# RasPi-powerSys.net
KiCad netlist of a schematic drawn in EAGLE
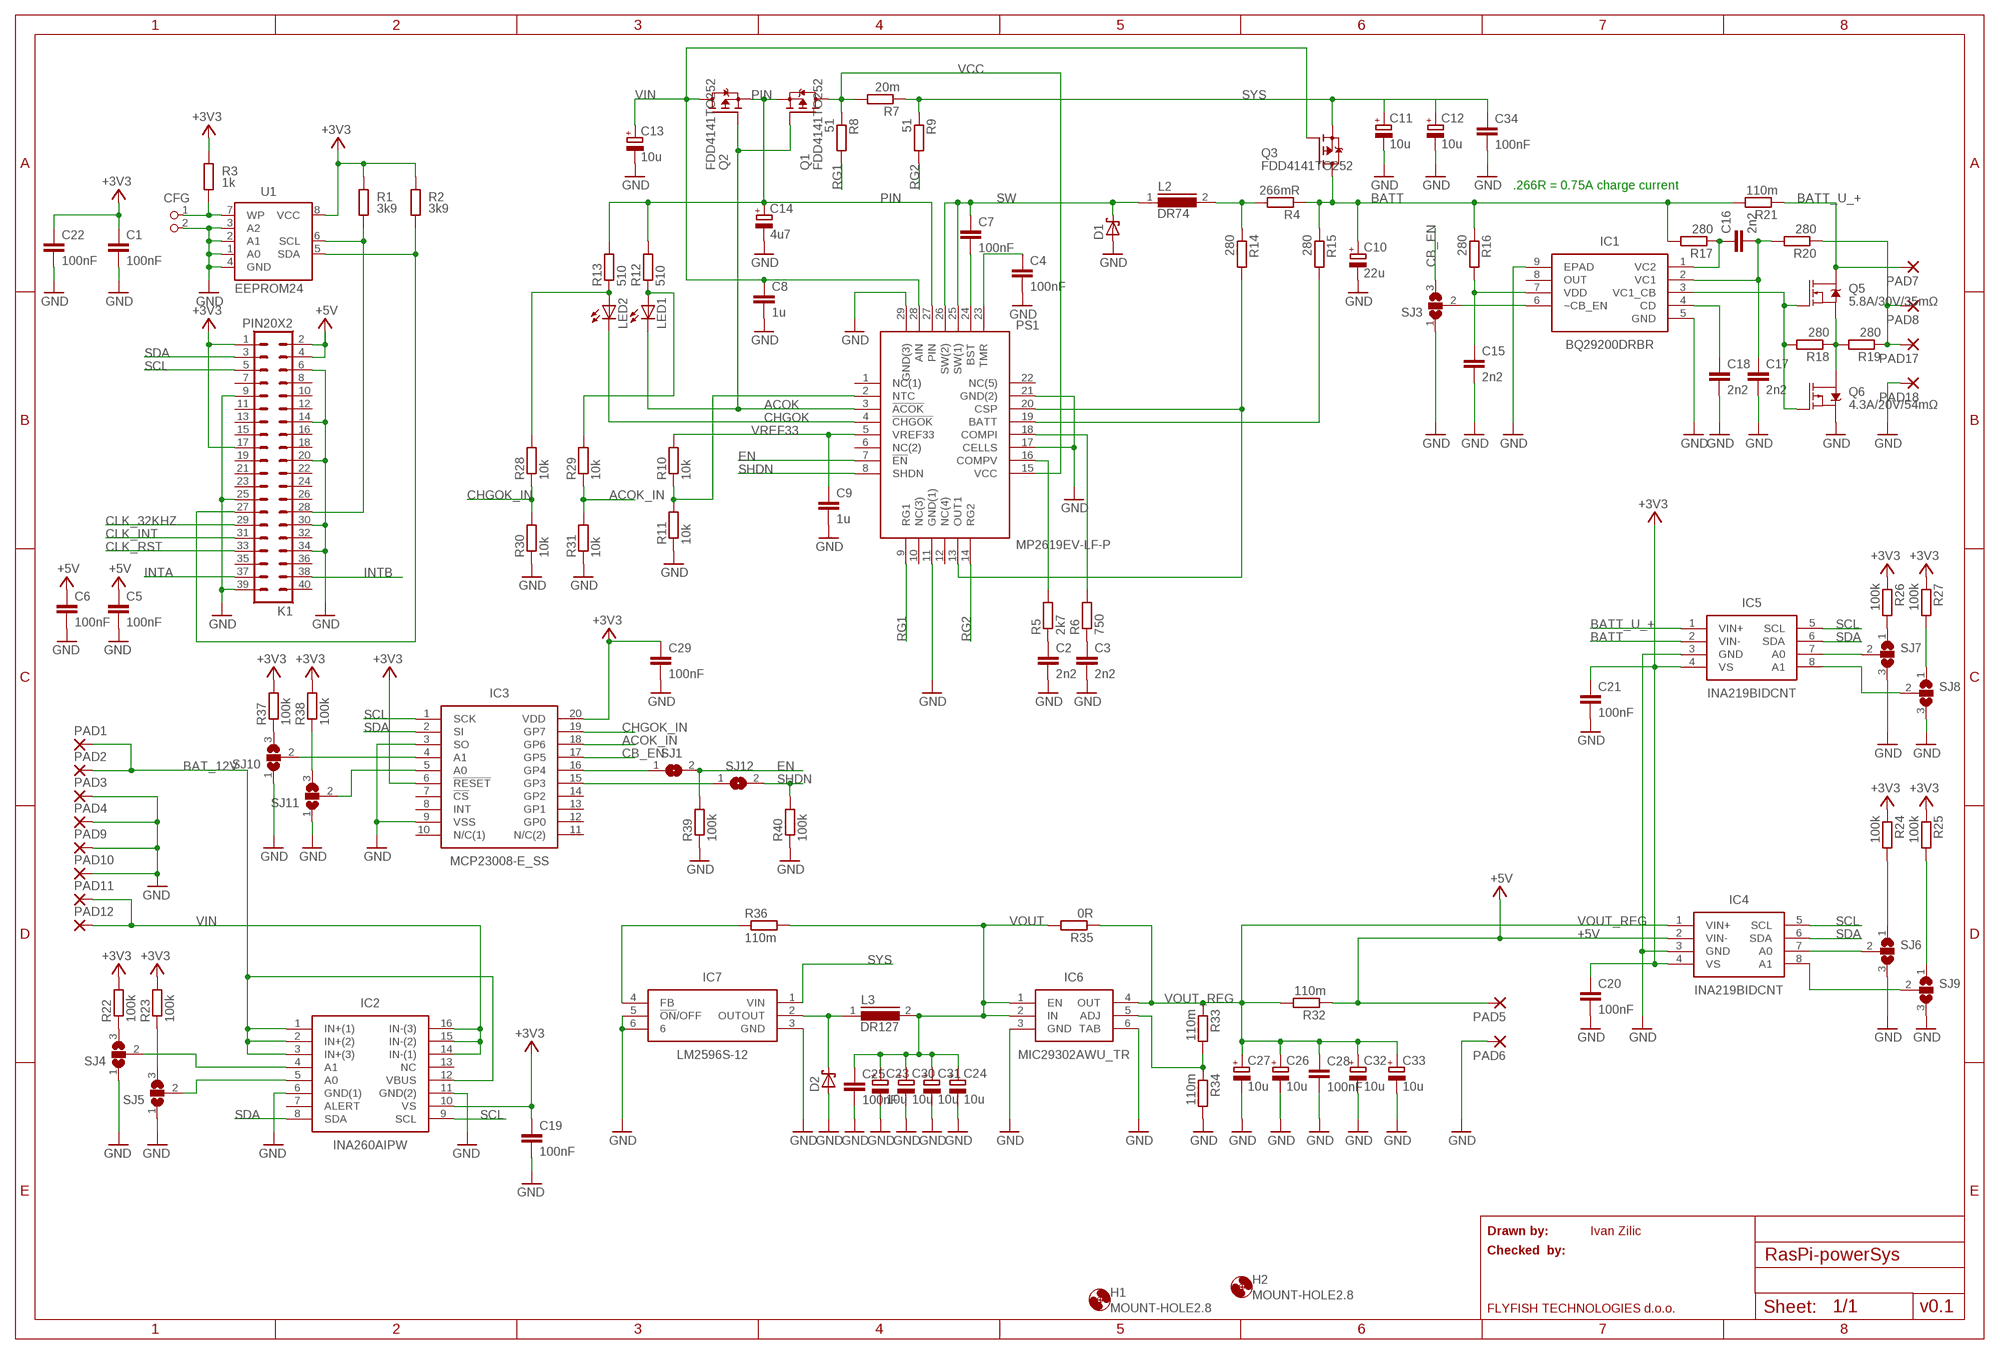
[diagram p0: schematic, sheet 1]

(export (version "E")
  (design (tool "Eeschema 10.0.6"))
  (components
    (comp (ref "C1")
      (value "100nF")
      (footprint "eagle-import:C0805K")
      (libsource (lib "eagle-import") (part "C-EUC0805K"))
    )
    (comp (ref "C2")
      (value "2n2")
      (footprint "eagle-import:C0805K")
      (libsource (lib "eagle-import") (part "C-EUC0805K"))
    )
    (comp (ref "C3")
      (value "2n2")
      (footprint "eagle-import:C0805K")
      (libsource (lib "eagle-import") (part "C-EUC0805K"))
    )
    (comp (ref "C4")
      (value "100nF")
      (footprint "eagle-import:C0805K")
      (libsource (lib "eagle-import") (part "C-EUC0805K"))
    )
    (comp (ref "C5")
      (value "100nF")
      (footprint "eagle-import:C0805K")
      (libsource (lib "eagle-import") (part "C-EUC0805K"))
    )
    (comp (ref "C6")
      (value "100nF")
      (footprint "eagle-import:C0805K")
      (libsource (lib "eagle-import") (part "C-EUC0805K"))
    )
    (comp (ref "C7")
      (value "100nF")
      (footprint "eagle-import:C0805K")
      (libsource (lib "eagle-import") (part "C-EUC0805K"))
    )
    (comp (ref "C8")
      (value "1u")
      (footprint "eagle-import:C0805K")
      (libsource (lib "eagle-import") (part "C-EUC0805K"))
    )
    (comp (ref "C9")
      (value "1u")
      (footprint "eagle-import:C0805K")
      (libsource (lib "eagle-import") (part "C-EUC0805K"))
    )
    (comp (ref "C10")
      (value "22u")
      (footprint "eagle-import:SMC_D")
      (libsource (lib "eagle-import") (part "CPOL-EUSMCD"))
    )
    (comp (ref "C11")
      (value "10u")
      (footprint "eagle-import:SMC_E")
      (libsource (lib "eagle-import") (part "CPOL-EUSMCE"))
    )
    (comp (ref "C12")
      (value "10u")
      (footprint "eagle-import:SMC_D")
      (libsource (lib "eagle-import") (part "CPOL-EUSMCD"))
    )
    (comp (ref "C13")
      (value "10u")
      (footprint "eagle-import:SMC_D")
      (libsource (lib "eagle-import") (part "CPOL-EUSMCD"))
    )
    (comp (ref "C14")
      (value "4u7")
      (footprint "eagle-import:SMC_D")
      (libsource (lib "eagle-import") (part "CPOL-EUSMCD"))
    )
    (comp (ref "C15")
      (value "2n2")
      (footprint "eagle-import:C0805K")
      (libsource (lib "eagle-import") (part "C-EUC0805K"))
    )
    (comp (ref "C16")
      (value "2n2")
      (footprint "eagle-import:C0805K")
      (libsource (lib "eagle-import") (part "C-EUC0805K"))
    )
    (comp (ref "C17")
      (value "2n2")
      (footprint "eagle-import:C0805K")
      (libsource (lib "eagle-import") (part "C-EUC0805K"))
    )
    (comp (ref "C18")
      (value "2n2")
      (footprint "eagle-import:C0805K")
      (libsource (lib "eagle-import") (part "C-EUC0805K"))
    )
    (comp (ref "C19")
      (value "100nF")
      (footprint "eagle-import:C0805K")
      (libsource (lib "eagle-import") (part "C-EUC0805K"))
    )
    (comp (ref "C20")
      (value "100nF")
      (footprint "eagle-import:C0805K")
      (libsource (lib "eagle-import") (part "C-EUC0805K"))
    )
    (comp (ref "C21")
      (value "100nF")
      (footprint "eagle-import:C0805K")
      (libsource (lib "eagle-import") (part "C-EUC0805K"))
    )
    (comp (ref "C22")
      (value "100nF")
      (footprint "eagle-import:C0805K")
      (libsource (lib "eagle-import") (part "C-EUC0805K"))
    )
    (comp (ref "C23")
      (value "10u")
      (footprint "eagle-import:SMC_E")
      (libsource (lib "eagle-import") (part "CPOL-EUSMCE"))
    )
    (comp (ref "C24")
      (value "10u")
      (footprint "eagle-import:SMC_E")
      (libsource (lib "eagle-import") (part "CPOL-EUSMCE"))
    )
    (comp (ref "C25")
      (value "100nF")
      (footprint "eagle-import:C0805K")
      (libsource (lib "eagle-import") (part "C-EUC0805K"))
    )
    (comp (ref "C26")
      (value "10u")
      (footprint "eagle-import:SMC_E")
      (libsource (lib "eagle-import") (part "CPOL-EUSMCE"))
    )
    (comp (ref "C27")
      (value "10u")
      (footprint "eagle-import:SMC_E")
      (libsource (lib "eagle-import") (part "CPOL-EUSMCE"))
    )
    (comp (ref "C28")
      (value "100nF")
      (footprint "eagle-import:C0805K")
      (libsource (lib "eagle-import") (part "C-EUC0805K"))
    )
    (comp (ref "C29")
      (value "100nF")
      (footprint "eagle-import:C0805K")
      (libsource (lib "eagle-import") (part "C-EUC0805K"))
    )
    (comp (ref "C30")
      (value "10u")
      (footprint "eagle-import:SMC_E")
      (libsource (lib "eagle-import") (part "CPOL-EUSMCE"))
    )
    (comp (ref "C31")
      (value "10u")
      (footprint "eagle-import:SMC_E")
      (libsource (lib "eagle-import") (part "CPOL-EUSMCE"))
    )
    (comp (ref "C32")
      (value "10u")
      (footprint "eagle-import:SMC_E")
      (libsource (lib "eagle-import") (part "CPOL-EUSMCE"))
    )
    (comp (ref "C33")
      (value "10u")
      (footprint "eagle-import:SMC_E")
      (libsource (lib "eagle-import") (part "CPOL-EUSMCE"))
    )
    (comp (ref "C34")
      (value "100nF")
      (footprint "eagle-import:C0805K")
      (libsource (lib "eagle-import") (part "C-EUC0805K"))
    )
    (comp (ref "CFG")
      (value "PIN2_100")
      (footprint "eagle-import:PIN_W_2")
      (libsource (lib "eagle-import") (part "PIN2_100"))
    )
    (comp (ref "D1")
      (value "SCHOTTKY-DIODESMD")
      (footprint "eagle-import:SMB")
      (libsource (lib "eagle-import") (part "SCHOTTKY-DIODESMD"))
    )
    (comp (ref "D2")
      (value "SCHOTTKY-DIODESMD")
      (footprint "eagle-import:SMB")
      (libsource (lib "eagle-import") (part "SCHOTTKY-DIODESMD"))
    )
    (comp (ref "H1")
      (value "MOUNT-HOLE2.8")
      (footprint "eagle-import:2,8")
      (libsource (lib "eagle-import") (part "MOUNT-HOLE2.8"))
    )
    (comp (ref "H2")
      (value "MOUNT-HOLE2.8")
      (footprint "eagle-import:2,8")
      (libsource (lib "eagle-import") (part "MOUNT-HOLE2.8"))
    )
    (comp (ref "IC1")
      (value "BQ29200DRBR")
      (footprint "eagle-import:SON65P300X300X100-9N")
      (libsource (lib "eagle-import") (part "BQ29200DRBR"))
    )
    (comp (ref "IC2")
      (value "INA260AIPW")
      (footprint "eagle-import:SOP65P640X120-16N")
      (libsource (lib "eagle-import") (part "INA260AIPW"))
    )
    (comp (ref "IC3")
      (value "MCP23008-E_SS")
      (footprint "eagle-import:SOP65P780X200-20N")
      (fields
        (field (name "MANUFACTURER_PART_NUMBER") "MCP23008-E/SS")
        (field (name "RS_PART_NUMBER") "7709707")
      )
      (libsource (lib "eagle-import") (part "MCP23008-E_SS"))
    )
    (comp (ref "IC4")
      (value "INA219BIDCNT")
      (footprint "eagle-import:SOT65P280X145-8N")
      (fields (field (name "RS_PART_NUMBER") "7300556P"))
      (libsource (lib "eagle-import") (part "INA219BIDCNT"))
    )
    (comp (ref "IC5")
      (value "INA219BIDCNT")
      (footprint "eagle-import:SOT65P280X145-8N")
      (fields (field (name "RS_PART_NUMBER") "7300556P"))
      (libsource (lib "eagle-import") (part "INA219BIDCNT"))
    )
    (comp (ref "IC6")
      (value "MIC29302AWU_TR")
      (footprint "eagle-import:5-PIN-TO-263(U)")
      (fields
        (field (name "MANUFACTURER_PART_NUMBER") "MIC29302AWU TR")
        (field (name "RS_PART_NUMBER") "8855990")
      )
      (libsource (lib "eagle-import") (part "MIC29302AWU_TR"))
    )
    (comp (ref "IC7")
      (value "LM2596S-12")
      (footprint "eagle-import:5-PIN-TO-263(U)")
      (libsource (lib "eagle-import") (part "LM2596S-12"))
    )
    (comp (ref "K1")
      (value "PIN20X2")
      (footprint "eagle-import:PIN_20X2")
      (libsource (lib "eagle-import") (part "PIN20X2"))
    )
    (comp (ref "L2")
      (value "DR74")
      (footprint "eagle-import:DR74")
      (libsource (lib "eagle-import") (part "DR74"))
    )
    (comp (ref "L3")
      (value "DR127")
      (footprint "eagle-import:DR127")
      (libsource (lib "eagle-import") (part "DR127"))
    )
    (comp (ref "LED1")
      (value "LEDCHIPLED_0805")
      (footprint "eagle-import:CHIPLED_0805")
      (libsource (lib "eagle-import") (part "LEDCHIPLED_0805"))
    )
    (comp (ref "LED2")
      (value "LEDCHIPLED_0805")
      (footprint "eagle-import:CHIPLED_0805")
      (libsource (lib "eagle-import") (part "LEDCHIPLED_0805"))
    )
    (comp (ref "PAD1")
      (value "3,81/1,4")
      (footprint "eagle-import:3,81_1,4")
      (libsource (lib "eagle-import") (part "3,81/1,4"))
    )
    (comp (ref "PAD2")
      (value "3,81/1,4")
      (footprint "eagle-import:3,81_1,4")
      (libsource (lib "eagle-import") (part "3,81/1,4"))
    )
    (comp (ref "PAD3")
      (value "3,81/1,4")
      (footprint "eagle-import:3,81_1,4")
      (libsource (lib "eagle-import") (part "3,81/1,4"))
    )
    (comp (ref "PAD4")
      (value "3,81/1,4")
      (footprint "eagle-import:3,81_1,4")
      (libsource (lib "eagle-import") (part "3,81/1,4"))
    )
    (comp (ref "PAD5")
      (value "3,81/1,4")
      (footprint "eagle-import:3,81_1,4")
      (libsource (lib "eagle-import") (part "3,81/1,4"))
    )
    (comp (ref "PAD6")
      (value "3,81/1,4")
      (footprint "eagle-import:3,81_1,4")
      (libsource (lib "eagle-import") (part "3,81/1,4"))
    )
    (comp (ref "PAD7")
      (value "3,81/1,4")
      (footprint "eagle-import:3,81_1,4")
      (libsource (lib "eagle-import") (part "3,81/1,4"))
    )
    (comp (ref "PAD8")
      (value "3,81/1,4")
      (footprint "eagle-import:3,81_1,4")
      (libsource (lib "eagle-import") (part "3,81/1,4"))
    )
    (comp (ref "PAD9")
      (value "3,81/1,4")
      (footprint "eagle-import:3,81_1,4")
      (libsource (lib "eagle-import") (part "3,81/1,4"))
    )
    (comp (ref "PAD10")
      (value "3,81/1,4")
      (footprint "eagle-import:3,81_1,4")
      (libsource (lib "eagle-import") (part "3,81/1,4"))
    )
    (comp (ref "PAD11")
      (value "3,81/1,4")
      (footprint "eagle-import:3,81_1,4")
      (libsource (lib "eagle-import") (part "3,81/1,4"))
    )
    (comp (ref "PAD12")
      (value "3,81/1,4")
      (footprint "eagle-import:3,81_1,4")
      (libsource (lib "eagle-import") (part "3,81/1,4"))
    )
    (comp (ref "PAD17")
      (value "3,81/1,4")
      (footprint "eagle-import:3,81_1,4")
      (libsource (lib "eagle-import") (part "3,81/1,4"))
    )
    (comp (ref "PAD18")
      (value "3,81/1,4")
      (footprint "eagle-import:3,81_1,4")
      (libsource (lib "eagle-import") (part "3,81/1,4"))
    )
    (comp (ref "PS1")
      (value "MP2619EV-LF-P")
      (footprint "eagle-import:QFN50P400X500X100-29N")
      (libsource (lib "eagle-import") (part "MP2619EV-LF-P"))
    )
    (comp (ref "Q1")
      (value "FDD4141TO252")
      (footprint "eagle-import:TO252")
      (libsource (lib "eagle-import") (part "FDD4141TO252"))
    )
    (comp (ref "Q2")
      (value "FDD4141TO252")
      (footprint "eagle-import:TO252")
      (libsource (lib "eagle-import") (part "FDD4141TO252"))
    )
    (comp (ref "Q3")
      (value "FDD4141TO252")
      (footprint "eagle-import:TO252")
      (libsource (lib "eagle-import") (part "FDD4141TO252"))
    )
    (comp (ref "Q5")
      (value "5.8A/30V/35mΩ")
      (footprint "eagle-import:SOT23-3")
      (libsource (lib "eagle-import") (part "MOSFET-NCH-AO3404A"))
    )
    (comp (ref "Q6")
      (value "4.3A/20V/54mΩ")
      (footprint "eagle-import:SOT23-3")
      (libsource (lib "eagle-import") (part "MOSFET_PCH-IRLML2244"))
    )
    (comp (ref "R1")
      (value "3k9")
      (footprint "eagle-import:M0805")
      (fields (field (name "TOLERANCE") "5%"))
      (libsource (lib "eagle-import") (part "resistor_348_R-EU_M0805"))
    )
    (comp (ref "R2")
      (value "3k9")
      (footprint "eagle-import:M0805")
      (fields (field (name "TOLERANCE") "5%"))
      (libsource (lib "eagle-import") (part "resistor_348_R-EU_M0805"))
    )
    (comp (ref "R3")
      (value "1k")
      (footprint "eagle-import:M0805")
      (fields (field (name "TOLERANCE") "5%"))
      (libsource (lib "eagle-import") (part "resistor_348_R-EU_M0805"))
    )
    (comp (ref "R4")
      (value "266mR")
      (footprint "eagle-import:R1206")
      (libsource (lib "eagle-import") (part "R-EU_R1206"))
    )
    (comp (ref "R5")
      (value "2k7")
      (footprint "eagle-import:R0805")
      (libsource (lib "eagle-import") (part "R-EU_R0805"))
    )
    (comp (ref "R6")
      (value "750")
      (footprint "eagle-import:R0805")
      (libsource (lib "eagle-import") (part "R-EU_R0805"))
    )
    (comp (ref "R7")
      (value "20m")
      (footprint "eagle-import:R0805")
      (libsource (lib "eagle-import") (part "R-EU_R0805"))
    )
    (comp (ref "R8")
      (value "51")
      (footprint "eagle-import:R0805")
      (libsource (lib "eagle-import") (part "R-EU_R0805"))
    )
    (comp (ref "R9")
      (value "51")
      (footprint "eagle-import:R0805")
      (libsource (lib "eagle-import") (part "R-EU_R0805"))
    )
    (comp (ref "R10")
      (value "10k")
      (footprint "eagle-import:R0805")
      (libsource (lib "eagle-import") (part "R-EU_R0805"))
    )
    (comp (ref "R11")
      (value "10k")
      (footprint "eagle-import:R0805")
      (libsource (lib "eagle-import") (part "R-EU_R0805"))
    )
    (comp (ref "R12")
      (value "510")
      (footprint "eagle-import:R0805")
      (libsource (lib "eagle-import") (part "R-EU_R0805"))
    )
    (comp (ref "R13")
      (value "510")
      (footprint "eagle-import:R0805")
      (libsource (lib "eagle-import") (part "R-EU_R0805"))
    )
    (comp (ref "R14")
      (value "280")
      (footprint "eagle-import:R0805")
      (libsource (lib "eagle-import") (part "R-EU_R0805"))
    )
    (comp (ref "R15")
      (value "280")
      (footprint "eagle-import:R0805")
      (libsource (lib "eagle-import") (part "R-EU_R0805"))
    )
    (comp (ref "R16")
      (value "280")
      (footprint "eagle-import:R0805")
      (libsource (lib "eagle-import") (part "R-EU_R0805"))
    )
    (comp (ref "R17")
      (value "280")
      (footprint "eagle-import:R1206")
      (libsource (lib "eagle-import") (part "R-EU_R1206"))
    )
    (comp (ref "R18")
      (value "280")
      (footprint "eagle-import:R1206")
      (libsource (lib "eagle-import") (part "R-EU_R1206"))
    )
    (comp (ref "R19")
      (value "280")
      (footprint "eagle-import:R1206")
      (libsource (lib "eagle-import") (part "R-EU_R1206"))
    )
    (comp (ref "R20")
      (value "280")
      (footprint "eagle-import:R1206")
      (libsource (lib "eagle-import") (part "R-EU_R1206"))
    )
    (comp (ref "R21")
      (value "110m")
      (footprint "eagle-import:R0805")
      (libsource (lib "eagle-import") (part "R-EU_R0805"))
    )
    (comp (ref "R22")
      (value "100k")
      (footprint "eagle-import:R0805")
      (libsource (lib "eagle-import") (part "R-EU_R0805"))
    )
    (comp (ref "R23")
      (value "100k")
      (footprint "eagle-import:R0805")
      (libsource (lib "eagle-import") (part "R-EU_R0805"))
    )
    (comp (ref "R24")
      (value "100k")
      (footprint "eagle-import:R0805")
      (libsource (lib "eagle-import") (part "R-EU_R0805"))
    )
    (comp (ref "R25")
      (value "100k")
      (footprint "eagle-import:R0805")
      (libsource (lib "eagle-import") (part "R-EU_R0805"))
    )
    (comp (ref "R26")
      (value "100k")
      (footprint "eagle-import:R0805")
      (libsource (lib "eagle-import") (part "R-EU_R0805"))
    )
    (comp (ref "R27")
      (value "100k")
      (footprint "eagle-import:R0805")
      (libsource (lib "eagle-import") (part "R-EU_R0805"))
    )
    (comp (ref "R28")
      (value "10k")
      (footprint "eagle-import:R0805")
      (libsource (lib "eagle-import") (part "R-EU_R0805"))
    )
    (comp (ref "R29")
      (value "10k")
      (footprint "eagle-import:R0805")
      (libsource (lib "eagle-import") (part "R-EU_R0805"))
    )
    (comp (ref "R30")
      (value "10k")
      (footprint "eagle-import:R0805")
      (libsource (lib "eagle-import") (part "R-EU_R0805"))
    )
    (comp (ref "R31")
      (value "10k")
      (footprint "eagle-import:R0805")
      (libsource (lib "eagle-import") (part "R-EU_R0805"))
    )
    (comp (ref "R32")
      (value "110m")
      (footprint "eagle-import:R1206")
      (libsource (lib "eagle-import") (part "R-EU_R1206"))
    )
    (comp (ref "R33")
      (value "110m")
      (footprint "eagle-import:R0805")
      (libsource (lib "eagle-import") (part "R-EU_R0805"))
    )
    (comp (ref "R34")
      (value "110m")
      (footprint "eagle-import:R0805")
      (libsource (lib "eagle-import") (part "R-EU_R0805"))
    )
    (comp (ref "R35")
      (value "0R")
      (footprint "eagle-import:R1206")
      (libsource (lib "eagle-import") (part "R-EU_R1206"))
    )
    (comp (ref "R36")
      (value "110m")
      (footprint "eagle-import:R0805")
      (libsource (lib "eagle-import") (part "R-EU_R0805"))
    )
    (comp (ref "R37")
      (value "100k")
      (footprint "eagle-import:R0805")
      (libsource (lib "eagle-import") (part "R-EU_R0805"))
    )
    (comp (ref "R38")
      (value "100k")
      (footprint "eagle-import:R0805")
      (libsource (lib "eagle-import") (part "R-EU_R0805"))
    )
    (comp (ref "R39")
      (value "100k")
      (footprint "eagle-import:R0805")
      (libsource (lib "eagle-import") (part "R-EU_R0805"))
    )
    (comp (ref "R40")
      (value "100k")
      (footprint "eagle-import:R0805")
      (libsource (lib "eagle-import") (part "R-EU_R0805"))
    )
    (comp (ref "SJ1") (value "SJ") (footprint "eagle-import:SJ") (libsource (lib "eagle-import") (part "SJ")))
    (comp (ref "SJ3")
      (value "SJ2W")
      (footprint "eagle-import:SJ_2")
      (libsource (lib "eagle-import") (part "SJ2W"))
    )
    (comp (ref "SJ4")
      (value "SJ2W")
      (footprint "eagle-import:SJ_2")
      (libsource (lib "eagle-import") (part "SJ2W"))
    )
    (comp (ref "SJ5")
      (value "SJ2W")
      (footprint "eagle-import:SJ_2")
      (libsource (lib "eagle-import") (part "SJ2W"))
    )
    (comp (ref "SJ6")
      (value "SJ2W")
      (footprint "eagle-import:SJ_2")
      (libsource (lib "eagle-import") (part "SJ2W"))
    )
    (comp (ref "SJ7")
      (value "SJ2W")
      (footprint "eagle-import:SJ_2")
      (libsource (lib "eagle-import") (part "SJ2W"))
    )
    (comp (ref "SJ8")
      (value "SJ2W")
      (footprint "eagle-import:SJ_2")
      (libsource (lib "eagle-import") (part "SJ2W"))
    )
    (comp (ref "SJ9")
      (value "SJ2W")
      (footprint "eagle-import:SJ_2")
      (libsource (lib "eagle-import") (part "SJ2W"))
    )
    (comp (ref "SJ10")
      (value "SJ2W")
      (footprint "eagle-import:SJ_2")
      (libsource (lib "eagle-import") (part "SJ2W"))
    )
    (comp (ref "SJ11")
      (value "SJ2W")
      (footprint "eagle-import:SJ_2")
      (libsource (lib "eagle-import") (part "SJ2W"))
    )
    (comp (ref "SJ12")
      (value "SJ")
      (footprint "eagle-import:SJ")
      (libsource (lib "eagle-import") (part "SJ"))
    )
    (comp (ref "U1")
      (value "EEPROM24")
      (footprint "eagle-import:SOIC8")
      (libsource (lib "eagle-import") (part "EEPROM24"))
    )
  )
  (nets
    (net (code "1") (name "+3V3") (class "Default")
      (node (ref "C1") (pin "1") (pinfunction "1_1") (pintype "passive"))
      (node (ref "C19") (pin "1") (pinfunction "1_1") (pintype "passive"))
      (node (ref "C20") (pin "1") (pinfunction "1_1") (pintype "passive"))
      (node (ref "C21") (pin "1") (pinfunction "1_1") (pintype "passive"))
      (node (ref "C22") (pin "1") (pinfunction "1_1") (pintype "passive"))
      (node (ref "C29") (pin "1") (pinfunction "1_1") (pintype "passive"))
      (node (ref "IC2") (pin "10") (pinfunction "VS_10") (pintype "power_in"))
      (node (ref "IC3") (pin "20") (pinfunction "VDD_20") (pintype "passive"))
      (node (ref "IC3") (pin "6") (pinfunction "~{RESET}_6") (pintype "passive"))
      (node (ref "IC4") (pin "4") (pinfunction "VS_4") (pintype "passive"))
      (node (ref "IC5") (pin "4") (pinfunction "VS_4") (pintype "passive"))
      (node (ref "K1") (pin "1") (pinfunction "1_1") (pintype "passive"))
      (node (ref "K1") (pin "17") (pinfunction "17_17") (pintype "passive"))
      (node (ref "R1") (pin "2") (pinfunction "2_2") (pintype "passive"))
      (node (ref "R2") (pin "2") (pinfunction "2_2") (pintype "passive"))
      (node (ref "R22") (pin "2") (pinfunction "2_2") (pintype "passive"))
      (node (ref "R23") (pin "2") (pinfunction "2_2") (pintype "passive"))
      (node (ref "R24") (pin "1") (pinfunction "1_1") (pintype "passive"))
      (node (ref "R25") (pin "1") (pinfunction "1_1") (pintype "passive"))
      (node (ref "R26") (pin "1") (pinfunction "1_1") (pintype "passive"))
      (node (ref "R27") (pin "1") (pinfunction "1_1") (pintype "passive"))
      (node (ref "R3") (pin "2") (pinfunction "2_2") (pintype "passive"))
      (node (ref "R37") (pin "2") (pinfunction "2_2") (pintype "passive"))
      (node (ref "R38") (pin "2") (pinfunction "2_2") (pintype "passive"))
      (node (ref "U1") (pin "8") (pinfunction "VCC_8") (pintype "power_in"))
    )
    (net (code "2") (name "+5V") (class "Default")
      (node (ref "C5") (pin "1") (pinfunction "1_1") (pintype "passive"))
      (node (ref "C6") (pin "1") (pinfunction "1_1") (pintype "passive"))
      (node (ref "IC4") (pin "2") (pinfunction "VIN-_2") (pintype "input"))
      (node (ref "K1") (pin "2") (pinfunction "2_2") (pintype "passive"))
      (node (ref "K1") (pin "4") (pinfunction "4_4") (pintype "passive"))
      (node (ref "PAD5") (pin "1") (pinfunction "P_1") (pintype "passive"))
      (node (ref "R32") (pin "1") (pinfunction "1_1") (pintype "passive"))
    )
    (net (code "3") (name "/ACOK") (class "Default")
      (node (ref "LED1") (pin "C") (pinfunction "C_C") (pintype "passive"))
      (node (ref "PS1") (pin "3") (pinfunction "~{ACOK}_3") (pintype "output"))
      (node (ref "Q1") (pin "1") (pinfunction "G_1") (pintype "passive"))
      (node (ref "Q2") (pin "1") (pinfunction "G_1") (pintype "passive"))
    )
    (net (code "4") (name "/ACOK_IN") (class "Default")
      (node (ref "IC3") (pin "18") (pinfunction "GP6_18") (pintype "passive"))
      (node (ref "R29") (pin "1") (pinfunction "1_1") (pintype "passive"))
      (node (ref "R31") (pin "2") (pinfunction "2_2") (pintype "passive"))
    )
    (net (code "5") (name "/BATT") (class "Default")
      (node (ref "C10") (pin "+") (pinfunction "+_+") (pintype "passive"))
      (node (ref "IC5") (pin "2") (pinfunction "VIN-_2") (pintype "input"))
      (node (ref "Q3") (pin "3") (pinfunction "D_3") (pintype "passive"))
      (node (ref "R15") (pin "1") (pinfunction "1_1") (pintype "passive"))
      (node (ref "R16") (pin "1") (pinfunction "1_1") (pintype "passive"))
      (node (ref "R17") (pin "2") (pinfunction "2_2") (pintype "passive"))
      (node (ref "R21") (pin "2") (pinfunction "2_2") (pintype "passive"))
      (node (ref "R4") (pin "1") (pinfunction "1_1") (pintype "passive"))
    )
    (net (code "6") (name "/BATT_U_+") (class "Default")
      (node (ref "IC5") (pin "1") (pinfunction "VIN+_1") (pintype "input"))
      (node (ref "PAD7") (pin "1") (pinfunction "P_1") (pintype "passive"))
      (node (ref "Q5") (pin "3") (pinfunction "D_3") (pintype "bidirectional"))
      (node (ref "R21") (pin "1") (pinfunction "1_1") (pintype "passive"))
    )
    (net (code "7") (name "/BAT_12V") (class "Default")
      (node (ref "IC2") (pin "1") (pinfunction "IN+(1)_1") (pintype "bidirectional"))
      (node (ref "IC2") (pin "12") (pinfunction "VBUS_12") (pintype "power_in"))
      (node (ref "IC2") (pin "2") (pinfunction "IN+(2)_2") (pintype "bidirectional"))
      (node (ref "IC2") (pin "3") (pinfunction "IN+(3)_3") (pintype "bidirectional"))
      (node (ref "PAD1") (pin "1") (pinfunction "P_1") (pintype "passive"))
      (node (ref "PAD2") (pin "1") (pinfunction "P_1") (pintype "passive"))
    )
    (net (code "8") (name "/CB_EN") (class "Default")
      (node (ref "IC3") (pin "17") (pinfunction "GP5_17") (pintype "passive"))
      (node (ref "SJ3") (pin "3") (pinfunction "3_3") (pintype "passive"))
    )
    (net (code "9") (name "/CHGOK") (class "Default")
      (node (ref "LED2") (pin "C") (pinfunction "C_C") (pintype "passive"))
      (node (ref "PS1") (pin "4") (pinfunction "~{CHGOK}_4") (pintype "output"))
    )
    (net (code "10") (name "/CHGOK_IN") (class "Default")
      (node (ref "IC3") (pin "19") (pinfunction "GP7_19") (pintype "passive"))
      (node (ref "R28") (pin "1") (pinfunction "1_1") (pintype "passive"))
      (node (ref "R30") (pin "2") (pinfunction "2_2") (pintype "passive"))
    )
    (net (code "11") (name "/CLK_32KHZ") (class "Default")
      (node (ref "K1") (pin "29") (pinfunction "29_29") (pintype "passive"))
    )
    (net (code "12") (name "/CLK_INT") (class "Default")
      (node (ref "K1") (pin "31") (pinfunction "31_31") (pintype "passive"))
    )
    (net (code "13") (name "/CLK_RST") (class "Default")
      (node (ref "K1") (pin "33") (pinfunction "33_33") (pintype "passive"))
    )
    (net (code "14") (name "/EN") (class "Default")
      (node (ref "PS1") (pin "7") (pinfunction "~{EN}_7") (pintype "input"))
      (node (ref "R39") (pin "2") (pinfunction "2_2") (pintype "passive"))
      (node (ref "SJ1") (pin "2") (pinfunction "2_2") (pintype "passive"))
    )
    (net (code "15") (name "/INTA") (class "Default")
      (node (ref "K1") (pin "37") (pinfunction "37_37") (pintype "passive"))
    )
    (net (code "16") (name "/INTB") (class "Default")
      (node (ref "K1") (pin "38") (pinfunction "38_38") (pintype "passive"))
    )
    (net (code "17") (name "/PIN") (class "Default")
      (node (ref "C14") (pin "+") (pinfunction "+_+") (pintype "passive"))
      (node (ref "PS1") (pin "27") (pinfunction "PIN_27") (pintype "power_in"))
      (node (ref "Q1") (pin "2") (pinfunction "S_2") (pintype "passive"))
      (node (ref "Q2") (pin "2") (pinfunction "S_2") (pintype "passive"))
      (node (ref "R12") (pin "2") (pinfunction "2_2") (pintype "passive"))
      (node (ref "R13") (pin "2") (pinfunction "2_2") (pintype "passive"))
    )
    (net (code "18") (name "/RG1") (class "Default")
      (node (ref "PS1") (pin "9") (pinfunction "RG1_9") (pintype "bidirectional"))
      (node (ref "R8") (pin "2") (pinfunction "2_2") (pintype "passive"))
    )
    (net (code "19") (name "/RG2") (class "Default")
      (node (ref "PS1") (pin "14") (pinfunction "RG2_14") (pintype "bidirectional"))
      (node (ref "R9") (pin "2") (pinfunction "2_2") (pintype "passive"))
    )
    (net (code "20") (name "/SCL") (class "Default")
      (node (ref "IC2") (pin "9") (pinfunction "SCL_9") (pintype "bidirectional"))
      (node (ref "IC3") (pin "1") (pinfunction "SCK_1") (pintype "passive"))
      (node (ref "IC4") (pin "5") (pinfunction "SCL_5") (pintype "passive"))
      (node (ref "IC5") (pin "5") (pinfunction "SCL_5") (pintype "passive"))
      (node (ref "K1") (pin "5") (pinfunction "5_5") (pintype "passive"))
    )
    (net (code "21") (name "/SDA") (class "Default")
      (node (ref "IC2") (pin "8") (pinfunction "SDA_8") (pintype "bidirectional"))
      (node (ref "IC3") (pin "2") (pinfunction "SI_2") (pintype "passive"))
      (node (ref "IC4") (pin "6") (pinfunction "SDA_6") (pintype "passive"))
      (node (ref "IC5") (pin "6") (pinfunction "SDA_6") (pintype "passive"))
      (node (ref "K1") (pin "3") (pinfunction "3_3") (pintype "passive"))
    )
    (net (code "22") (name "/SHDN") (class "Default")
      (node (ref "PS1") (pin "8") (pinfunction "SHDN_8") (pintype "input"))
      (node (ref "R40") (pin "2") (pinfunction "2_2") (pintype "passive"))
      (node (ref "SJ12") (pin "2") (pinfunction "2_2") (pintype "passive"))
    )
    (net (code "23") (name "/SW") (class "Default")
      (node (ref "C7") (pin "1") (pinfunction "1_1") (pintype "passive"))
      (node (ref "D1") (pin "C") (pinfunction "C_C") (pintype "passive"))
      (node (ref "L2") (pin "1") (pinfunction "1_1") (pintype "passive"))
      (node (ref "PS1") (pin "25") (pinfunction "SW(1)_25") (pintype "output"))
      (node (ref "PS1") (pin "26") (pinfunction "SW(2)_26") (pintype "output"))
    )
    (net (code "24") (name "/SYS") (class "Default")
      (node (ref "C11") (pin "+") (pinfunction "+_+") (pintype "passive"))
      (node (ref "C12") (pin "+") (pinfunction "+_+") (pintype "passive"))
      (node (ref "C34") (pin "1") (pinfunction "1_1") (pintype "passive"))
      (node (ref "IC7") (pin "1") (pinfunction "VIN_1") (pintype "input"))
      (node (ref "Q3") (pin "2") (pinfunction "S_2") (pintype "passive"))
      (node (ref "R7") (pin "1") (pinfunction "1_1") (pintype "passive"))
      (node (ref "R9") (pin "1") (pinfunction "1_1") (pintype "passive"))
    )
    (net (code "25") (name "/VCC") (class "Default")
      (node (ref "PS1") (pin "15") (pinfunction "VCC_15") (pintype "power_in"))
      (node (ref "Q1") (pin "3") (pinfunction "D_3") (pintype "passive"))
      (node (ref "R7") (pin "2") (pinfunction "2_2") (pintype "passive"))
      (node (ref "R8") (pin "1") (pinfunction "1_1") (pintype "passive"))
    )
    (net (code "26") (name "/VIN") (class "Default")
      (node (ref "C13") (pin "+") (pinfunction "+_+") (pintype "passive"))
      (node (ref "C8") (pin "1") (pinfunction "1_1") (pintype "passive"))
      (node (ref "IC2") (pin "14") (pinfunction "IN-(1)_14") (pintype "bidirectional"))
      (node (ref "IC2") (pin "15") (pinfunction "IN-(2)_15") (pintype "bidirectional"))
      (node (ref "IC2") (pin "16") (pinfunction "IN-(3)_16") (pintype "bidirectional"))
      (node (ref "PAD11") (pin "1") (pinfunction "P_1") (pintype "passive"))
      (node (ref "PAD12") (pin "1") (pinfunction "P_1") (pintype "passive"))
      (node (ref "PS1") (pin "28") (pinfunction "AIN_28") (pintype "power_in"))
      (node (ref "Q2") (pin "3") (pinfunction "D_3") (pintype "passive"))
      (node (ref "Q3") (pin "1") (pinfunction "G_1") (pintype "passive"))
    )
    (net (code "27") (name "/VOUT") (class "Default")
      (node (ref "C23") (pin "+") (pinfunction "+_+") (pintype "passive"))
      (node (ref "C24") (pin "+") (pinfunction "+_+") (pintype "passive"))
      (node (ref "C25") (pin "1") (pinfunction "1_1") (pintype "passive"))
      (node (ref "C30") (pin "+") (pinfunction "+_+") (pintype "passive"))
      (node (ref "C31") (pin "+") (pinfunction "+_+") (pintype "passive"))
      (node (ref "IC6") (pin "1") (pinfunction "EN_1") (pintype "passive"))
      (node (ref "IC6") (pin "2") (pinfunction "IN_2") (pintype "passive"))
      (node (ref "L3") (pin "2") (pinfunction "2_2") (pintype "passive"))
      (node (ref "R35") (pin "2") (pinfunction "2_2") (pintype "passive"))
      (node (ref "R36") (pin "2") (pinfunction "2_2") (pintype "passive"))
    )
    (net (code "28") (name "/VOUT_REG") (class "Default")
      (node (ref "C26") (pin "+") (pinfunction "+_+") (pintype "passive"))
      (node (ref "C27") (pin "+") (pinfunction "+_+") (pintype "passive"))
      (node (ref "C28") (pin "1") (pinfunction "1_1") (pintype "passive"))
      (node (ref "C32") (pin "+") (pinfunction "+_+") (pintype "passive"))
      (node (ref "C33") (pin "+") (pinfunction "+_+") (pintype "passive"))
      (node (ref "IC4") (pin "1") (pinfunction "VIN+_1") (pintype "input"))
      (node (ref "IC6") (pin "4") (pinfunction "OUT_4") (pintype "passive"))
      (node (ref "R32") (pin "2") (pinfunction "2_2") (pintype "passive"))
      (node (ref "R33") (pin "1") (pinfunction "1_1") (pintype "passive"))
      (node (ref "R35") (pin "1") (pinfunction "1_1") (pintype "passive"))
    )
    (net (code "29") (name "/VREF33") (class "Default")
      (node (ref "C9") (pin "1") (pinfunction "1_1") (pintype "passive"))
      (node (ref "PS1") (pin "5") (pinfunction "VREF33_5") (pintype "output"))
      (node (ref "R10") (pin "2") (pinfunction "2_2") (pintype "passive"))
    )
    (net (code "30") (name "GND") (class "Default")
      (node (ref "C1") (pin "2") (pinfunction "2_2") (pintype "passive"))
      (node (ref "C10") (pin "-") (pinfunction "-_-") (pintype "passive"))
      (node (ref "C11") (pin "-") (pinfunction "-_-") (pintype "passive"))
      (node (ref "C12") (pin "-") (pinfunction "-_-") (pintype "passive"))
      (node (ref "C13") (pin "-") (pinfunction "-_-") (pintype "passive"))
      (node (ref "C14") (pin "-") (pinfunction "-_-") (pintype "passive"))
      (node (ref "C15") (pin "2") (pinfunction "2_2") (pintype "passive"))
      (node (ref "C17") (pin "2") (pinfunction "2_2") (pintype "passive"))
      (node (ref "C18") (pin "2") (pinfunction "2_2") (pintype "passive"))
      (node (ref "C19") (pin "2") (pinfunction "2_2") (pintype "passive"))
      (node (ref "C2") (pin "2") (pinfunction "2_2") (pintype "passive"))
      (node (ref "C20") (pin "2") (pinfunction "2_2") (pintype "passive"))
      (node (ref "C21") (pin "2") (pinfunction "2_2") (pintype "passive"))
      (node (ref "C22") (pin "2") (pinfunction "2_2") (pintype "passive"))
      (node (ref "C23") (pin "-") (pinfunction "-_-") (pintype "passive"))
      (node (ref "C24") (pin "-") (pinfunction "-_-") (pintype "passive"))
      (node (ref "C25") (pin "2") (pinfunction "2_2") (pintype "passive"))
      (node (ref "C26") (pin "-") (pinfunction "-_-") (pintype "passive"))
      (node (ref "C27") (pin "-") (pinfunction "-_-") (pintype "passive"))
      (node (ref "C28") (pin "2") (pinfunction "2_2") (pintype "passive"))
      (node (ref "C29") (pin "2") (pinfunction "2_2") (pintype "passive"))
      (node (ref "C3") (pin "2") (pinfunction "2_2") (pintype "passive"))
      (node (ref "C30") (pin "-") (pinfunction "-_-") (pintype "passive"))
      (node (ref "C31") (pin "-") (pinfunction "-_-") (pintype "passive"))
      (node (ref "C32") (pin "-") (pinfunction "-_-") (pintype "passive"))
      (node (ref "C33") (pin "-") (pinfunction "-_-") (pintype "passive"))
      (node (ref "C34") (pin "2") (pinfunction "2_2") (pintype "passive"))
      (node (ref "C4") (pin "2") (pinfunction "2_2") (pintype "passive"))
      (node (ref "C5") (pin "2") (pinfunction "2_2") (pintype "passive"))
      (node (ref "C6") (pin "2") (pinfunction "2_2") (pintype "passive"))
      (node (ref "C8") (pin "2") (pinfunction "2_2") (pintype "passive"))
      (node (ref "C9") (pin "2") (pinfunction "2_2") (pintype "passive"))
      (node (ref "CFG") (pin "2") (pinfunction "2_2") (pintype "passive"))
      (node (ref "D1") (pin "A") (pinfunction "A_A") (pintype "passive"))
      (node (ref "D2") (pin "A") (pinfunction "A_A") (pintype "passive"))
      (node (ref "IC1") (pin "5") (pinfunction "GND_5") (pintype "passive"))
      (node (ref "IC1") (pin "9") (pinfunction "EPAD_9") (pintype "passive"))
      (node (ref "IC2") (pin "11") (pinfunction "GND(2)_11") (pintype "power_in"))
      (node (ref "IC2") (pin "6") (pinfunction "GND(1)_6") (pintype "power_in"))
      (node (ref "IC3") (pin "3") (pinfunction "SO_3") (pintype "passive"))
      (node (ref "IC3") (pin "9") (pinfunction "VSS_9") (pintype "passive"))
      (node (ref "IC4") (pin "3") (pinfunction "GND_3") (pintype "power_in"))
      (node (ref "IC5") (pin "3") (pinfunction "GND_3") (pintype "power_in"))
      (node (ref "IC6") (pin "3") (pinfunction "GND_3") (pintype "passive"))
      (node (ref "IC6") (pin "6") (pinfunction "TAB_6") (pintype "passive"))
      (node (ref "IC7") (pin "3") (pinfunction "GND_3") (pintype "passive"))
      (node (ref "IC7") (pin "5") (pinfunction "~{ON}/OFF_5") (pintype "passive"))
      (node (ref "IC7") (pin "6") (pinfunction "6_6") (pintype "passive"))
      (node (ref "K1") (pin "14") (pinfunction "14_14") (pintype "passive"))
      (node (ref "K1") (pin "20") (pinfunction "20_20") (pintype "passive"))
      (node (ref "K1") (pin "25") (pinfunction "25_25") (pintype "passive"))
      (node (ref "K1") (pin "30") (pinfunction "30_30") (pintype "passive"))
      (node (ref "K1") (pin "34") (pinfunction "34_34") (pintype "passive"))
      (node (ref "K1") (pin "39") (pinfunction "39_39") (pintype "passive"))
      (node (ref "K1") (pin "6") (pinfunction "6_6") (pintype "passive"))
      (node (ref "K1") (pin "9") (pinfunction "9_9") (pintype "passive"))
      (node (ref "PAD10") (pin "1") (pinfunction "P_1") (pintype "passive"))
      (node (ref "PAD18") (pin "1") (pinfunction "P_1") (pintype "passive"))
      (node (ref "PAD3") (pin "1") (pinfunction "P_1") (pintype "passive"))
      (node (ref "PAD4") (pin "1") (pinfunction "P_1") (pintype "passive"))
      (node (ref "PAD6") (pin "1") (pinfunction "P_1") (pintype "passive"))
      (node (ref "PAD9") (pin "1") (pinfunction "P_1") (pintype "passive"))
      (node (ref "PS1") (pin "11") (pinfunction "GND(1)_11") (pintype "power_in"))
      (node (ref "PS1") (pin "17") (pinfunction "CELLS_17") (pintype "input"))
      (node (ref "PS1") (pin "21") (pinfunction "GND(2)_21") (pintype "power_in"))
      (node (ref "PS1") (pin "29") (pinfunction "GND(3)_29") (pintype "passive"))
      (node (ref "Q6") (pin "2") (pinfunction "S_2") (pintype "bidirectional"))
      (node (ref "R11") (pin "1") (pinfunction "1_1") (pintype "passive"))
      (node (ref "R30") (pin "1") (pinfunction "1_1") (pintype "passive"))
      (node (ref "R31") (pin "1") (pinfunction "1_1") (pintype "passive"))
      (node (ref "R34") (pin "2") (pinfunction "2_2") (pintype "passive"))
      (node (ref "R39") (pin "1") (pinfunction "1_1") (pintype "passive"))
      (node (ref "R40") (pin "1") (pinfunction "1_1") (pintype "passive"))
      (node (ref "SJ10") (pin "1") (pinfunction "1_1") (pintype "passive"))
      (node (ref "SJ11") (pin "1") (pinfunction "1_1") (pintype "passive"))
      (node (ref "SJ3") (pin "1") (pinfunction "1_1") (pintype "passive"))
      (node (ref "SJ4") (pin "1") (pinfunction "1_1") (pintype "passive"))
      (node (ref "SJ5") (pin "1") (pinfunction "1_1") (pintype "passive"))
      (node (ref "SJ6") (pin "3") (pinfunction "3_3") (pintype "passive"))
      (node (ref "SJ7") (pin "3") (pinfunction "3_3") (pintype "passive"))
      (node (ref "SJ8") (pin "3") (pinfunction "3_3") (pintype "passive"))
      (node (ref "SJ9") (pin "3") (pinfunction "3_3") (pintype "passive"))
      (node (ref "U1") (pin "1") (pinfunction "A0_1") (pintype "input"))
      (node (ref "U1") (pin "2") (pinfunction "A1_2") (pintype "input"))
      (node (ref "U1") (pin "3") (pinfunction "A2_3") (pintype "input"))
      (node (ref "U1") (pin "4") (pinfunction "GND_4") (pintype "power_in"))
    )
    (net (code "31") (name "Net-(C2-Pad1)") (class "Default")
      (node (ref "C2") (pin "1") (pinfunction "1_1") (pintype "passive"))
      (node (ref "R5") (pin "1") (pinfunction "1_1") (pintype "passive"))
    )
    (net (code "32") (name "Net-(C3-Pad1)") (class "Default")
      (node (ref "C3") (pin "1") (pinfunction "1_1") (pintype "passive"))
      (node (ref "R6") (pin "1") (pinfunction "1_1") (pintype "passive"))
    )
    (net (code "33") (name "Net-(IC1-CD)") (class "Default")
      (node (ref "C18") (pin "1") (pinfunction "1_1") (pintype "passive"))
      (node (ref "IC1") (pin "4") (pinfunction "CD_4") (pintype "passive"))
    )
    (net (code "34") (name "Net-(IC1-VC1)") (class "Default")
      (node (ref "C16") (pin "2") (pinfunction "2_2") (pintype "passive"))
      (node (ref "C17") (pin "1") (pinfunction "1_1") (pintype "passive"))
      (node (ref "IC1") (pin "2") (pinfunction "VC1_2") (pintype "passive"))
      (node (ref "R20") (pin "2") (pinfunction "2_2") (pintype "passive"))
    )
    (net (code "35") (name "Net-(IC1-VC1_CB)") (class "Default")
      (node (ref "IC1") (pin "3") (pinfunction "VC1_CB_3") (pintype "passive"))
      (node (ref "Q5") (pin "1") (pinfunction "G_1") (pintype "bidirectional"))
      (node (ref "Q6") (pin "1") (pinfunction "G_1") (pintype "bidirectional"))
      (node (ref "R18") (pin "2") (pinfunction "2_2") (pintype "passive"))
    )
    (net (code "36") (name "Net-(IC1-VC2)") (class "Default")
      (node (ref "C16") (pin "1") (pinfunction "1_1") (pintype "passive"))
      (node (ref "IC1") (pin "1") (pinfunction "VC2_1") (pintype "passive"))
      (node (ref "R17") (pin "1") (pinfunction "1_1") (pintype "passive"))
    )
    (net (code "37") (name "Net-(IC1-VDD)") (class "Default")
      (node (ref "C15") (pin "1") (pinfunction "1_1") (pintype "passive"))
      (node (ref "IC1") (pin "7") (pinfunction "VDD_7") (pintype "passive"))
      (node (ref "R16") (pin "2") (pinfunction "2_2") (pintype "passive"))
    )
    (net (code "38") (name "Net-(IC1-~{CB_EN})") (class "Default")
      (node (ref "IC1") (pin "6") (pinfunction "~{CB_EN}_6") (pintype "passive"))
      (node (ref "SJ3") (pin "2") (pinfunction "2_2") (pintype "passive"))
    )
    (net (code "39") (name "Net-(IC2-A0)") (class "Default")
      (node (ref "IC2") (pin "5") (pinfunction "A0_5") (pintype "input"))
      (node (ref "SJ5") (pin "2") (pinfunction "2_2") (pintype "passive"))
    )
    (net (code "40") (name "Net-(IC2-A1)") (class "Default")
      (node (ref "IC2") (pin "4") (pinfunction "A1_4") (pintype "input"))
      (node (ref "SJ4") (pin "2") (pinfunction "2_2") (pintype "passive"))
    )
    (net (code "41") (name "Net-(IC3-A0)") (class "Default")
      (node (ref "IC3") (pin "5") (pinfunction "A0_5") (pintype "passive"))
      (node (ref "SJ11") (pin "2") (pinfunction "2_2") (pintype "passive"))
    )
    (net (code "42") (name "Net-(IC3-A1)") (class "Default")
      (node (ref "IC3") (pin "4") (pinfunction "A1_4") (pintype "passive"))
      (node (ref "SJ10") (pin "2") (pinfunction "2_2") (pintype "passive"))
    )
    (net (code "43") (name "Net-(IC3-GP3)") (class "Default")
      (node (ref "IC3") (pin "15") (pinfunction "GP3_15") (pintype "passive"))
      (node (ref "SJ12") (pin "1") (pinfunction "1_1") (pintype "passive"))
    )
    (net (code "44") (name "Net-(IC3-GP4)") (class "Default")
      (node (ref "IC3") (pin "16") (pinfunction "GP4_16") (pintype "passive"))
      (node (ref "SJ1") (pin "1") (pinfunction "1_1") (pintype "passive"))
    )
    (net (code "45") (name "Net-(IC4-A0)") (class "Default")
      (node (ref "IC4") (pin "7") (pinfunction "A0_7") (pintype "passive"))
      (node (ref "SJ6") (pin "2") (pinfunction "2_2") (pintype "passive"))
    )
    (net (code "46") (name "Net-(IC4-A1)") (class "Default")
      (node (ref "IC4") (pin "8") (pinfunction "A1_8") (pintype "passive"))
      (node (ref "SJ9") (pin "2") (pinfunction "2_2") (pintype "passive"))
    )
    (net (code "47") (name "Net-(IC5-A0)") (class "Default")
      (node (ref "IC5") (pin "7") (pinfunction "A0_7") (pintype "passive"))
      (node (ref "SJ7") (pin "2") (pinfunction "2_2") (pintype "passive"))
    )
    (net (code "48") (name "Net-(IC5-A1)") (class "Default")
      (node (ref "IC5") (pin "8") (pinfunction "A1_8") (pintype "passive"))
      (node (ref "SJ8") (pin "2") (pinfunction "2_2") (pintype "passive"))
    )
    (net (code "49") (name "Net-(IC6-ADJ)") (class "Default")
      (node (ref "IC6") (pin "5") (pinfunction "ADJ_5") (pintype "passive"))
      (node (ref "R33") (pin "2") (pinfunction "2_2") (pintype "passive"))
      (node (ref "R34") (pin "1") (pinfunction "1_1") (pintype "passive"))
    )
    (net (code "50") (name "Net-(IC7-FB)") (class "Default")
      (node (ref "IC7") (pin "4") (pinfunction "FB_4") (pintype "passive"))
      (node (ref "R36") (pin "1") (pinfunction "1_1") (pintype "passive"))
    )
    (net (code "51") (name "Net-(IC7-OUTOUT)") (class "Default")
      (node (ref "D2") (pin "C") (pinfunction "C_C") (pintype "passive"))
      (node (ref "IC7") (pin "2") (pinfunction "OUTOUT_2") (pintype "output"))
      (node (ref "L3") (pin "1") (pinfunction "1_1") (pintype "passive"))
    )
    (net (code "52") (name "Net-(L2-Pad2)") (class "Default")
      (node (ref "L2") (pin "2") (pinfunction "2_2") (pintype "passive"))
      (node (ref "R14") (pin "1") (pinfunction "1_1") (pintype "passive"))
      (node (ref "R4") (pin "2") (pinfunction "2_2") (pintype "passive"))
    )
    (net (code "53") (name "Net-(LED1-PadA)") (class "Default")
      (node (ref "LED1") (pin "A") (pinfunction "A_A") (pintype "passive"))
      (node (ref "R12") (pin "1") (pinfunction "1_1") (pintype "passive"))
      (node (ref "R29") (pin "2") (pinfunction "2_2") (pintype "passive"))
    )
    (net (code "54") (name "Net-(LED2-PadA)") (class "Default")
      (node (ref "LED2") (pin "A") (pinfunction "A_A") (pintype "passive"))
      (node (ref "R13") (pin "1") (pinfunction "1_1") (pintype "passive"))
      (node (ref "R28") (pin "2") (pinfunction "2_2") (pintype "passive"))
    )
    (net (code "55") (name "Net-(PAD17-P)") (class "Default")
      (node (ref "PAD17") (pin "1") (pinfunction "P_1") (pintype "passive"))
      (node (ref "PAD8") (pin "1") (pinfunction "P_1") (pintype "passive"))
      (node (ref "R19") (pin "1") (pinfunction "1_1") (pintype "passive"))
      (node (ref "R20") (pin "1") (pinfunction "1_1") (pintype "passive"))
    )
    (net (code "56") (name "Net-(PS1-BATT)") (class "Default")
      (node (ref "PS1") (pin "19") (pinfunction "BATT_19") (pintype "power_in"))
      (node (ref "R15") (pin "2") (pinfunction "2_2") (pintype "passive"))
    )
    (net (code "57") (name "Net-(PS1-BST)") (class "Default")
      (node (ref "C7") (pin "2") (pinfunction "2_2") (pintype "passive"))
      (node (ref "PS1") (pin "24") (pinfunction "BST_24") (pintype "bidirectional"))
    )
    (net (code "58") (name "Net-(PS1-COMPI)") (class "Default")
      (node (ref "PS1") (pin "18") (pinfunction "COMPI_18") (pintype "bidirectional"))
      (node (ref "R6") (pin "2") (pinfunction "2_2") (pintype "passive"))
    )
    (net (code "59") (name "Net-(PS1-COMPV)") (class "Default")
      (node (ref "PS1") (pin "16") (pinfunction "COMPV_16") (pintype "bidirectional"))
      (node (ref "R5") (pin "2") (pinfunction "2_2") (pintype "passive"))
    )
    (net (code "60") (name "Net-(PS1-CSP)") (class "Default")
      (node (ref "PS1") (pin "13") (pinfunction "OUT1_13") (pintype "output"))
      (node (ref "PS1") (pin "20") (pinfunction "CSP_20") (pintype "input"))
      (node (ref "R14") (pin "2") (pinfunction "2_2") (pintype "passive"))
    )
    (net (code "61") (name "Net-(PS1-NTC)") (class "Default")
      (node (ref "PS1") (pin "2") (pinfunction "NTC_2") (pintype "input"))
      (node (ref "R10") (pin "1") (pinfunction "1_1") (pintype "passive"))
      (node (ref "R11") (pin "2") (pinfunction "2_2") (pintype "passive"))
    )
    (net (code "62") (name "Net-(PS1-TMR)") (class "Default")
      (node (ref "C4") (pin "1") (pinfunction "1_1") (pintype "passive"))
      (node (ref "PS1") (pin "23") (pinfunction "TMR_23") (pintype "input"))
    )
    (net (code "63") (name "Net-(Q5-S)") (class "Default")
      (node (ref "Q5") (pin "2") (pinfunction "S_2") (pintype "bidirectional"))
      (node (ref "Q6") (pin "3") (pinfunction "D_3") (pintype "bidirectional"))
      (node (ref "R18") (pin "1") (pinfunction "1_1") (pintype "passive"))
      (node (ref "R19") (pin "2") (pinfunction "2_2") (pintype "passive"))
    )
    (net (code "64") (name "Net-(R22-Pad1)") (class "Default")
      (node (ref "R22") (pin "1") (pinfunction "1_1") (pintype "passive"))
      (node (ref "SJ4") (pin "3") (pinfunction "3_3") (pintype "passive"))
    )
    (net (code "65") (name "Net-(R23-Pad1)") (class "Default")
      (node (ref "R23") (pin "1") (pinfunction "1_1") (pintype "passive"))
      (node (ref "SJ5") (pin "3") (pinfunction "3_3") (pintype "passive"))
    )
    (net (code "66") (name "Net-(R24-Pad2)") (class "Default")
      (node (ref "R24") (pin "2") (pinfunction "2_2") (pintype "passive"))
      (node (ref "SJ6") (pin "1") (pinfunction "1_1") (pintype "passive"))
    )
    (net (code "67") (name "Net-(R25-Pad2)") (class "Default")
      (node (ref "R25") (pin "2") (pinfunction "2_2") (pintype "passive"))
      (node (ref "SJ9") (pin "1") (pinfunction "1_1") (pintype "passive"))
    )
    (net (code "68") (name "Net-(R26-Pad2)") (class "Default")
      (node (ref "R26") (pin "2") (pinfunction "2_2") (pintype "passive"))
      (node (ref "SJ7") (pin "1") (pinfunction "1_1") (pintype "passive"))
    )
    (net (code "69") (name "Net-(R27-Pad2)") (class "Default")
      (node (ref "R27") (pin "2") (pinfunction "2_2") (pintype "passive"))
      (node (ref "SJ8") (pin "1") (pinfunction "1_1") (pintype "passive"))
    )
    (net (code "70") (name "Net-(R37-Pad1)") (class "Default")
      (node (ref "R37") (pin "1") (pinfunction "1_1") (pintype "passive"))
      (node (ref "SJ10") (pin "3") (pinfunction "3_3") (pintype "passive"))
    )
    (net (code "71") (name "Net-(R38-Pad1)") (class "Default")
      (node (ref "R38") (pin "1") (pinfunction "1_1") (pintype "passive"))
      (node (ref "SJ11") (pin "3") (pinfunction "3_3") (pintype "passive"))
    )
    (net (code "72") (name "Net-(U1-SCL)") (class "Default")
      (node (ref "K1") (pin "28") (pinfunction "28_28") (pintype "passive"))
      (node (ref "R1") (pin "1") (pinfunction "1_1") (pintype "passive"))
      (node (ref "U1") (pin "6") (pinfunction "SCL_6") (pintype "input"))
    )
    (net (code "73") (name "Net-(U1-SDA)") (class "Default")
      (node (ref "K1") (pin "27") (pinfunction "27_27") (pintype "passive"))
      (node (ref "R2") (pin "1") (pinfunction "1_1") (pintype "passive"))
      (node (ref "U1") (pin "5") (pinfunction "SDA_5") (pintype "bidirectional"))
    )
    (net (code "74") (name "Net-(U1-WP)") (class "Default")
      (node (ref "CFG") (pin "1") (pinfunction "1_1") (pintype "passive"))
      (node (ref "R3") (pin "1") (pinfunction "1_1") (pintype "passive"))
      (node (ref "U1") (pin "7") (pinfunction "WP_7") (pintype "input"))
    )
    (net (code "75") (name "unconnected-(IC1-OUT-Pad8)") (class "Default")
      (node (ref "IC1") (pin "8") (pinfunction "OUT_8") (pintype "passive"))
    )
    (net (code "76") (name "unconnected-(IC2-ALERT-Pad7)") (class "Default")
      (node (ref "IC2") (pin "7") (pinfunction "ALERT_7") (pintype "output"))
    )
    (net (code "77") (name "unconnected-(IC2-NC-Pad13)") (class "Default")
      (node (ref "IC2") (pin "13") (pinfunction "NC_13") (pintype "no_connect"))
    )
    (net (code "78") (name "unconnected-(IC3-GP0-Pad12)") (class "Default")
      (node (ref "IC3") (pin "12") (pinfunction "GP0_12") (pintype "passive"))
    )
    (net (code "79") (name "unconnected-(IC3-GP1-Pad13)") (class "Default")
      (node (ref "IC3") (pin "13") (pinfunction "GP1_13") (pintype "passive"))
    )
    (net (code "80") (name "unconnected-(IC3-GP2-Pad14)") (class "Default")
      (node (ref "IC3") (pin "14") (pinfunction "GP2_14") (pintype "passive"))
    )
    (net (code "81") (name "unconnected-(IC3-INT-Pad8)") (class "Default")
      (node (ref "IC3") (pin "8") (pinfunction "INT_8") (pintype "passive"))
    )
    (net (code "82") (name "unconnected-(IC3-N{slash}C(1)-Pad10)") (class "Default")
      (node (ref "IC3") (pin "10") (pinfunction "N/C(1)_10") (pintype "passive"))
    )
    (net (code "83") (name "unconnected-(IC3-N{slash}C(2)-Pad11)") (class "Default")
      (node (ref "IC3") (pin "11") (pinfunction "N/C(2)_11") (pintype "passive"))
    )
    (net (code "84") (name "unconnected-(IC3-~{CS}-Pad7)") (class "Default")
      (node (ref "IC3") (pin "7") (pinfunction "~{CS}_7") (pintype "passive"))
    )
    (net (code "85") (name "unconnected-(K1-Pad7)") (class "Default")
      (node (ref "K1") (pin "7") (pinfunction "7_7") (pintype "passive"))
    )
    (net (code "86") (name "unconnected-(K1-Pad8)") (class "Default")
      (node (ref "K1") (pin "8") (pinfunction "8_8") (pintype "passive"))
    )
    (net (code "87") (name "unconnected-(K1-Pad10)") (class "Default")
      (node (ref "K1") (pin "10") (pinfunction "10_10") (pintype "passive"))
    )
    (net (code "88") (name "unconnected-(K1-Pad11)") (class "Default")
      (node (ref "K1") (pin "11") (pinfunction "11_11") (pintype "passive"))
    )
    (net (code "89") (name "unconnected-(K1-Pad12)") (class "Default")
      (node (ref "K1") (pin "12") (pinfunction "12_12") (pintype "passive"))
    )
    (net (code "90") (name "unconnected-(K1-Pad13)") (class "Default")
      (node (ref "K1") (pin "13") (pinfunction "13_13") (pintype "passive"))
    )
    (net (code "91") (name "unconnected-(K1-Pad15)") (class "Default")
      (node (ref "K1") (pin "15") (pinfunction "15_15") (pintype "passive"))
    )
    (net (code "92") (name "unconnected-(K1-Pad16)") (class "Default")
      (node (ref "K1") (pin "16") (pinfunction "16_16") (pintype "passive"))
    )
    (net (code "93") (name "unconnected-(K1-Pad18)") (class "Default")
      (node (ref "K1") (pin "18") (pinfunction "18_18") (pintype "passive"))
    )
    (net (code "94") (name "unconnected-(K1-Pad19)") (class "Default")
      (node (ref "K1") (pin "19") (pinfunction "19_19") (pintype "passive"))
    )
    (net (code "95") (name "unconnected-(K1-Pad21)") (class "Default")
      (node (ref "K1") (pin "21") (pinfunction "21_21") (pintype "passive"))
    )
    (net (code "96") (name "unconnected-(K1-Pad22)") (class "Default")
      (node (ref "K1") (pin "22") (pinfunction "22_22") (pintype "passive"))
    )
    (net (code "97") (name "unconnected-(K1-Pad23)") (class "Default")
      (node (ref "K1") (pin "23") (pinfunction "23_23") (pintype "passive"))
    )
    (net (code "98") (name "unconnected-(K1-Pad24)") (class "Default")
      (node (ref "K1") (pin "24") (pinfunction "24_24") (pintype "passive"))
    )
    (net (code "99") (name "unconnected-(K1-Pad26)") (class "Default")
      (node (ref "K1") (pin "26") (pinfunction "26_26") (pintype "passive"))
    )
    (net (code "100") (name "unconnected-(K1-Pad32)") (class "Default")
      (node (ref "K1") (pin "32") (pinfunction "32_32") (pintype "passive"))
    )
    (net (code "101") (name "unconnected-(K1-Pad35)") (class "Default")
      (node (ref "K1") (pin "35") (pinfunction "35_35") (pintype "passive"))
    )
    (net (code "102") (name "unconnected-(K1-Pad36)") (class "Default")
      (node (ref "K1") (pin "36") (pinfunction "36_36") (pintype "passive"))
    )
    (net (code "103") (name "unconnected-(K1-Pad40)") (class "Default")
      (node (ref "K1") (pin "40") (pinfunction "40_40") (pintype "passive"))
    )
    (net (code "104") (name "unconnected-(PS1-NC(1)-Pad1)") (class "Default")
      (node (ref "PS1") (pin "1") (pinfunction "NC(1)_1") (pintype "passive"))
    )
    (net (code "105") (name "unconnected-(PS1-NC(2)-Pad6)") (class "Default")
      (node (ref "PS1") (pin "6") (pinfunction "NC(2)_6") (pintype "passive"))
    )
    (net (code "106") (name "unconnected-(PS1-NC(3)-Pad10)") (class "Default")
      (node (ref "PS1") (pin "10") (pinfunction "NC(3)_10") (pintype "passive"))
    )
    (net (code "107") (name "unconnected-(PS1-NC(4)-Pad12)") (class "Default")
      (node (ref "PS1") (pin "12") (pinfunction "NC(4)_12") (pintype "passive"))
    )
    (net (code "108") (name "unconnected-(PS1-NC(5)-Pad22)") (class "Default")
      (node (ref "PS1") (pin "22") (pinfunction "NC(5)_22") (pintype "passive"))
    )
  )
)
